# StripConnector.net
KiCad netlist of a schematic drawn in EAGLE
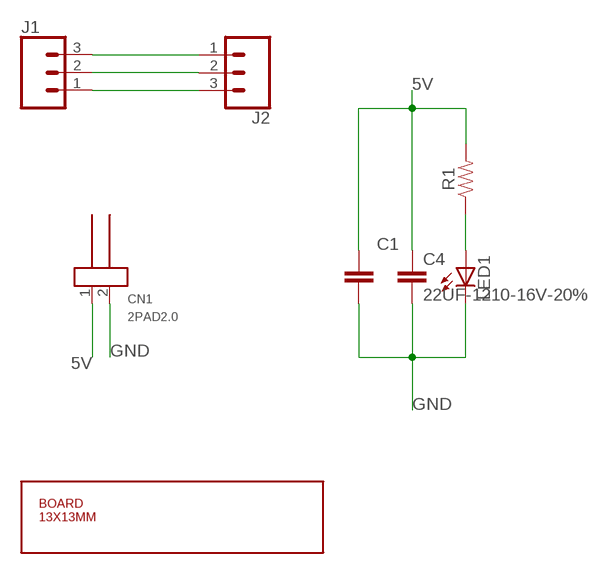
[diagram p0: schematic, sheet 1]

(export (version "E")
  (design (tool "Eeschema 10.0.6"))
  (components
    (comp (ref "C1")
      (value "CAPACITOR_NPOL-0805")
      (footprint "eagle-import:C805")
      (libsource (lib "eagle-import") (part "CAPACITOR_NPOL-0805"))
    )
    (comp (ref "C4")
      (value "22UF-1210-16V-20%")
      (footprint "eagle-import:1210")
      (libsource (lib "eagle-import") (part "22UF-1210-16V-20%"))
    )
    (comp (ref "CN1")
      (value "2PAD2.0")
      (footprint "eagle-import:2POLE_P2.0")
      (libsource (lib "eagle-import") (part "2PAD2.0"))
    )
    (comp (ref "J1")
      (value "CONN_03LONGPADS")
      (footprint "eagle-import:1X03_LONGPADS")
      (libsource (lib "eagle-import") (part "CONN_03LONGPADS"))
    )
    (comp (ref "J2")
      (value "CONN_03LONGPADS")
      (footprint "eagle-import:1X03_LONGPADS")
      (libsource (lib "eagle-import") (part "CONN_03LONGPADS"))
    )
    (comp (ref "LED1")
      (value "LED-0805")
      (footprint "eagle-import:LED-805")
      (libsource (lib "eagle-import") (part "LED-0805"))
    )
    (comp (ref "R1")
      (value "RESISTOR0805")
      (footprint "eagle-import:0805")
      (libsource (lib "eagle-import") (part "RESISTOR0805"))
    )
    (comp (ref "U$1")
      (value "BOARD_13X13MM")
      (footprint "eagle-import:13X13")
      (libsource (lib "eagle-import") (part "BOARD_13X13MM"))
    )
  )
  (nets
    (net (code "1") (name "/5V") (class "Default")
      (node (ref "C1") (pin "1") (pinfunction "1_1") (pintype "passive"))
      (node (ref "C4") (pin "1") (pinfunction "1_1") (pintype "passive"))
      (node (ref "CN1") (pin "1") (pinfunction "P$1_1") (pintype "bidirectional"))
      (node (ref "J1") (pin "1") (pinfunction "1_1") (pintype "passive"))
      (node (ref "J2") (pin "3") (pinfunction "3_3") (pintype "passive"))
      (node (ref "R1") (pin "2") (pinfunction "2_2") (pintype "passive"))
    )
    (net (code "2") (name "/GND") (class "Default")
      (node (ref "C1") (pin "2") (pinfunction "2_2") (pintype "passive"))
      (node (ref "C4") (pin "2") (pinfunction "2_2") (pintype "passive"))
      (node (ref "CN1") (pin "2") (pinfunction "P$2_2") (pintype "bidirectional"))
      (node (ref "J1") (pin "3") (pinfunction "3_3") (pintype "passive"))
      (node (ref "J2") (pin "1") (pinfunction "1_1") (pintype "passive"))
      (node (ref "LED1") (pin "C") (pinfunction "C_C") (pintype "passive"))
    )
    (net (code "3") (name "Net-(J1-Pad2)") (class "Default")
      (node (ref "J1") (pin "2") (pinfunction "2_2") (pintype "passive"))
      (node (ref "J2") (pin "2") (pinfunction "2_2") (pintype "passive"))
    )
    (net (code "4") (name "Net-(LED1-PadA)") (class "Default")
      (node (ref "LED1") (pin "A") (pinfunction "A_A") (pintype "passive"))
      (node (ref "R1") (pin "1") (pinfunction "1_1") (pintype "passive"))
    )
  )
)
